# hygiea_v0_0.net
KiCad netlist of a schematic drawn in EAGLE
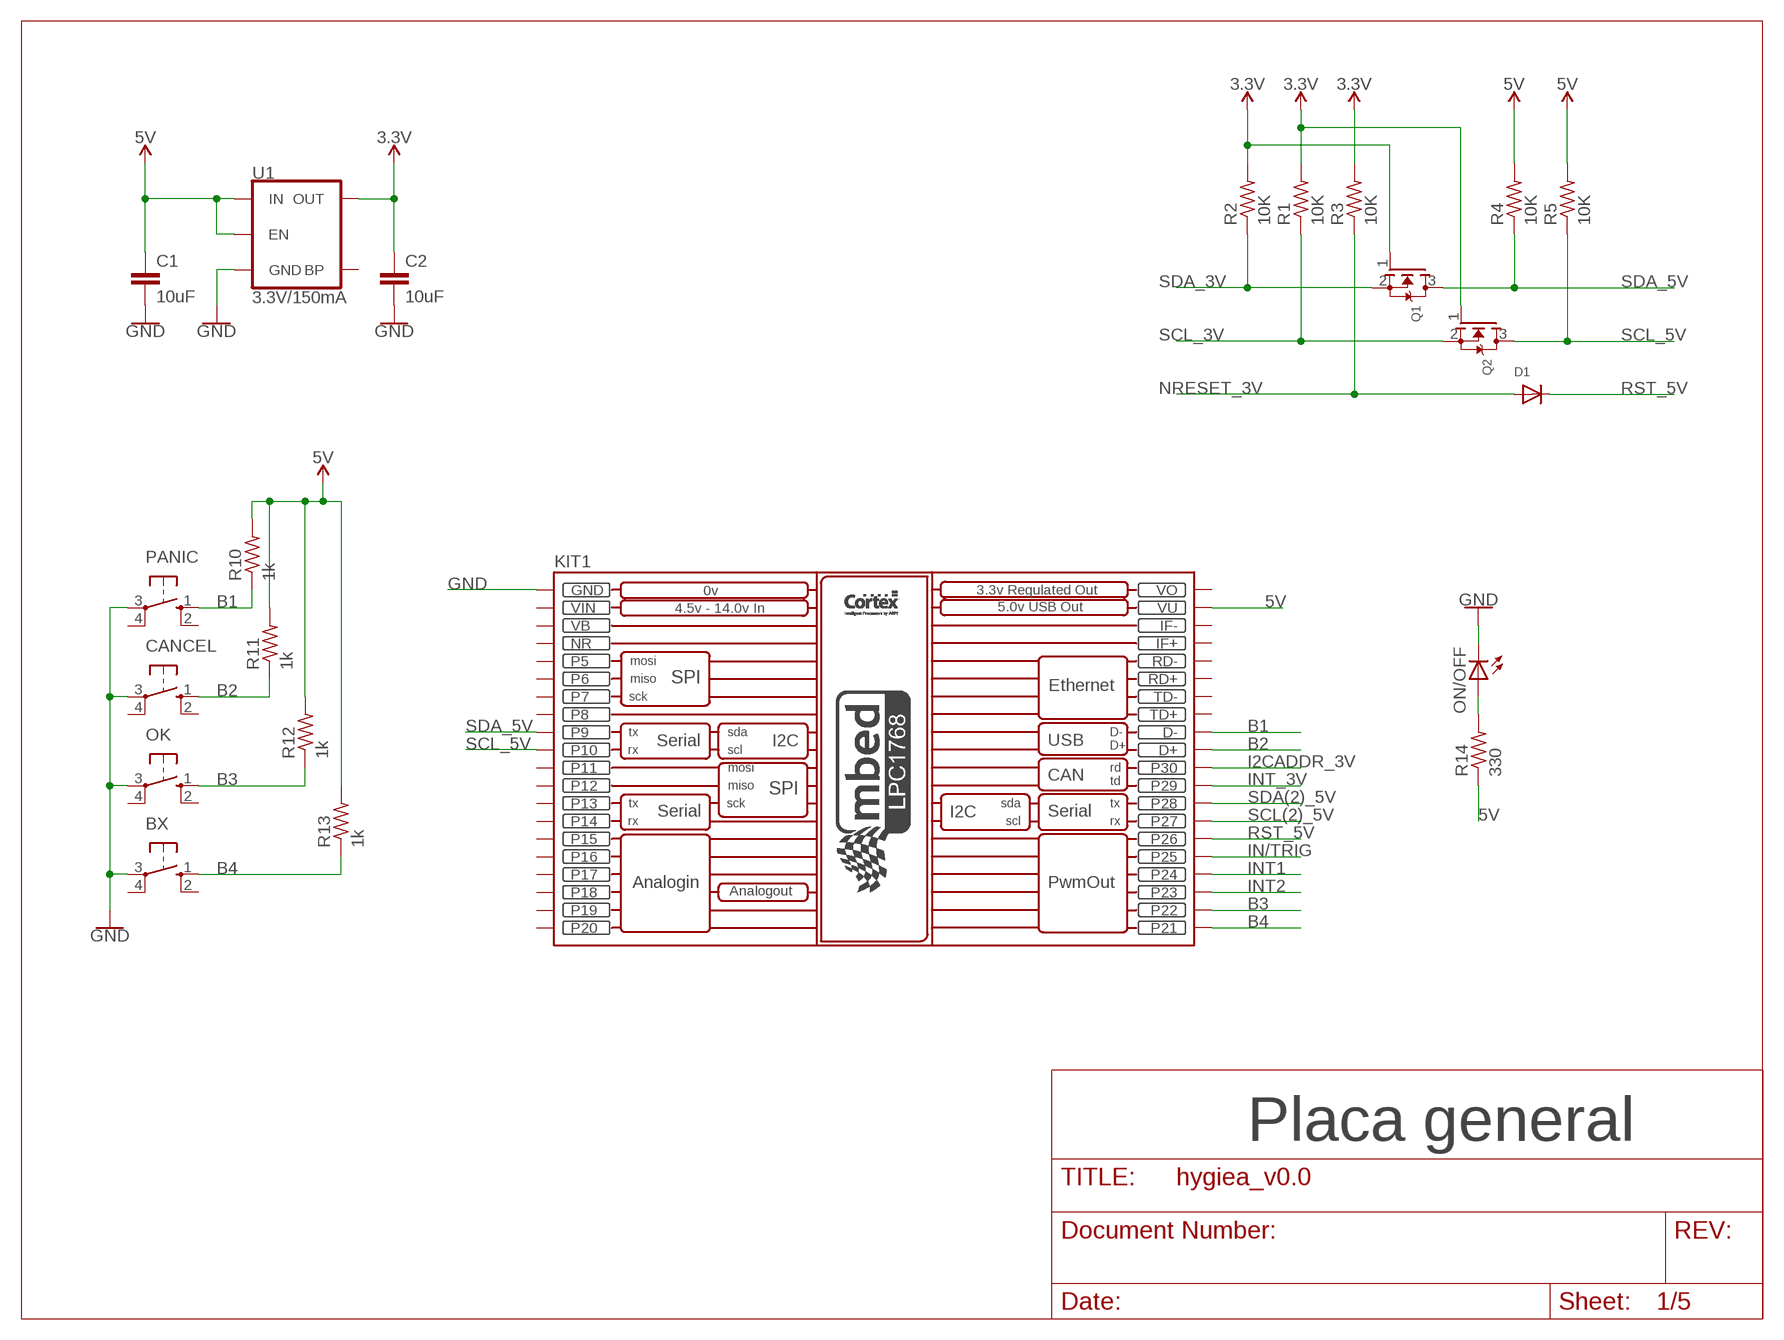
[diagram p0: schematic, sheet 1]
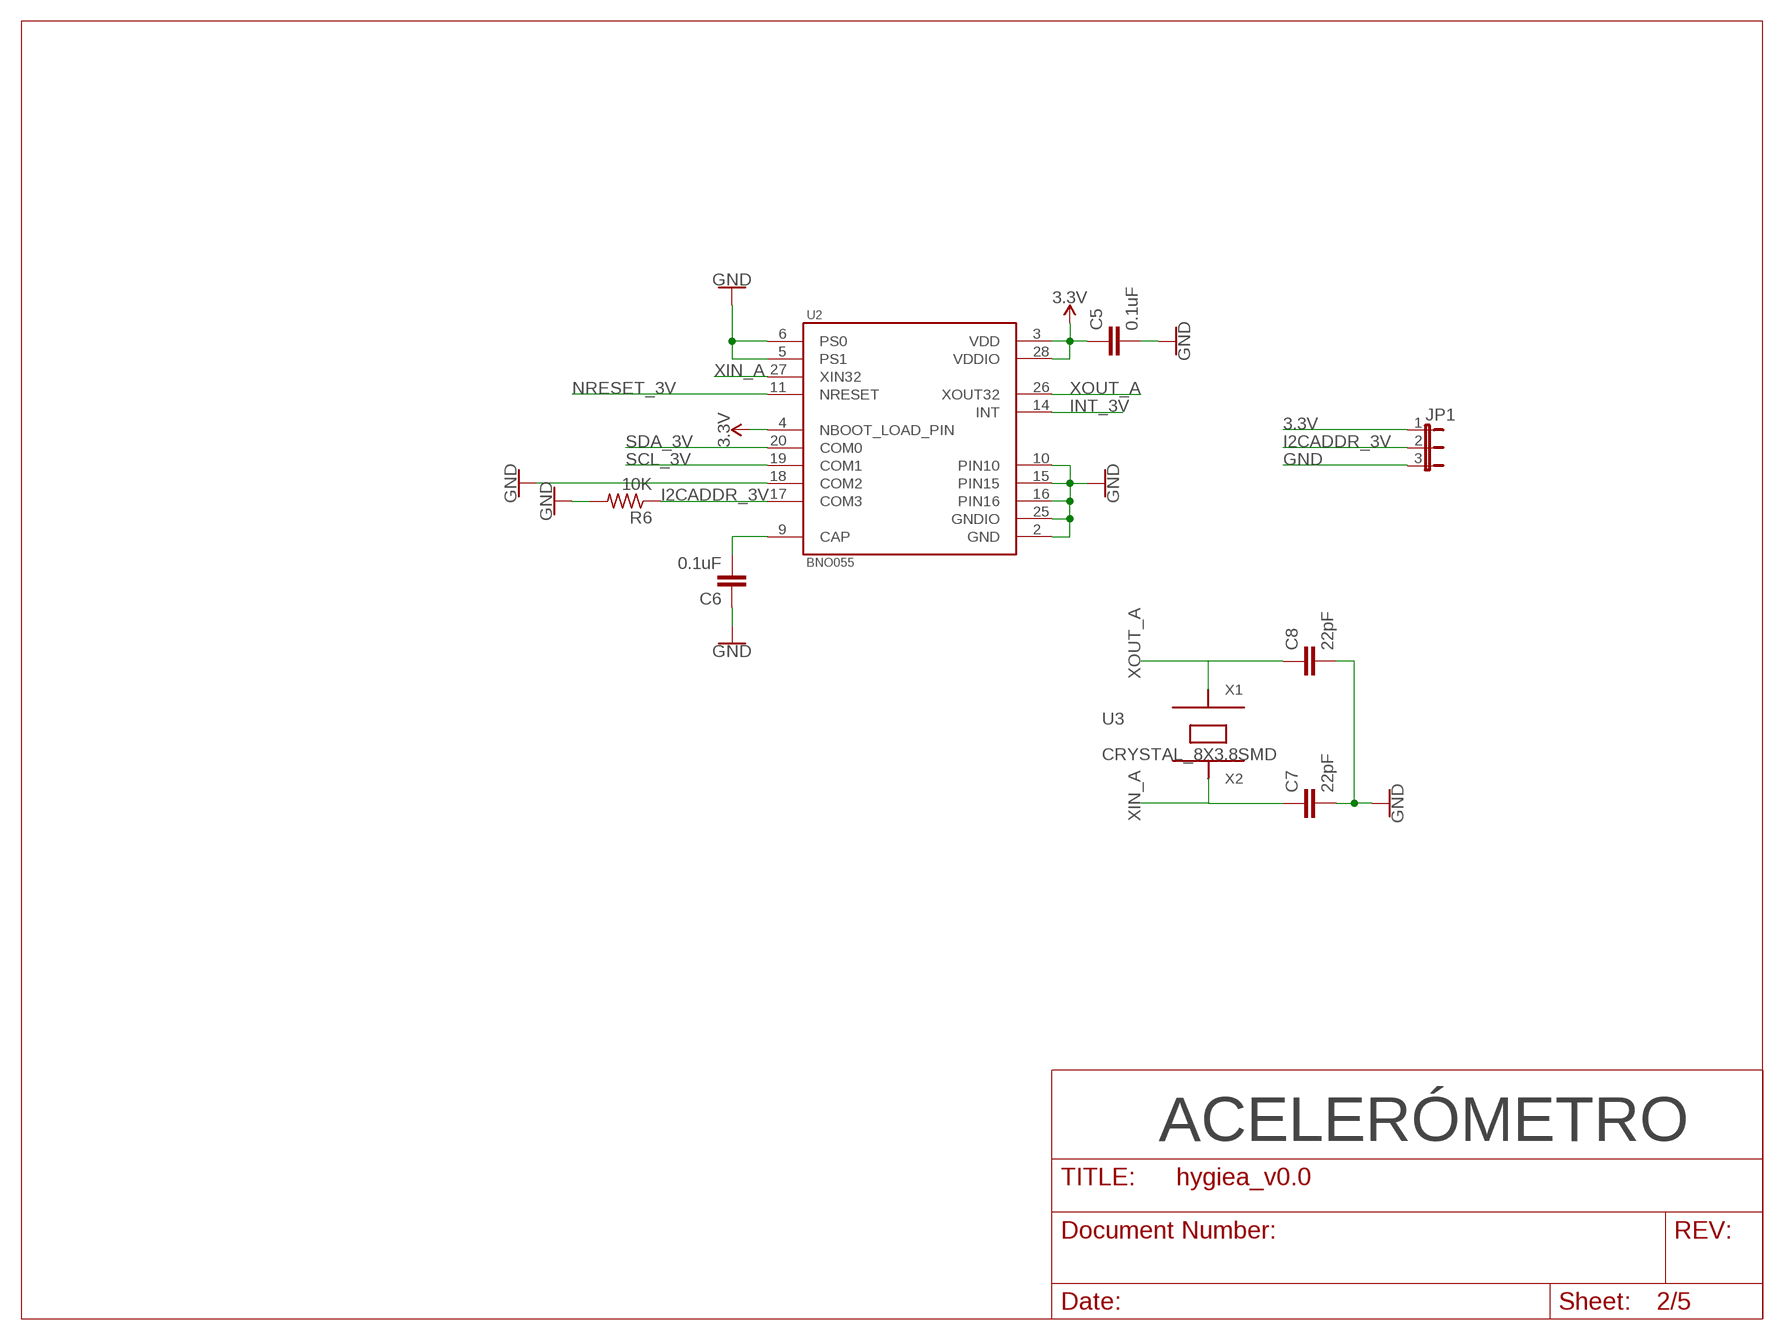
[diagram p1: schematic, sheet 2]
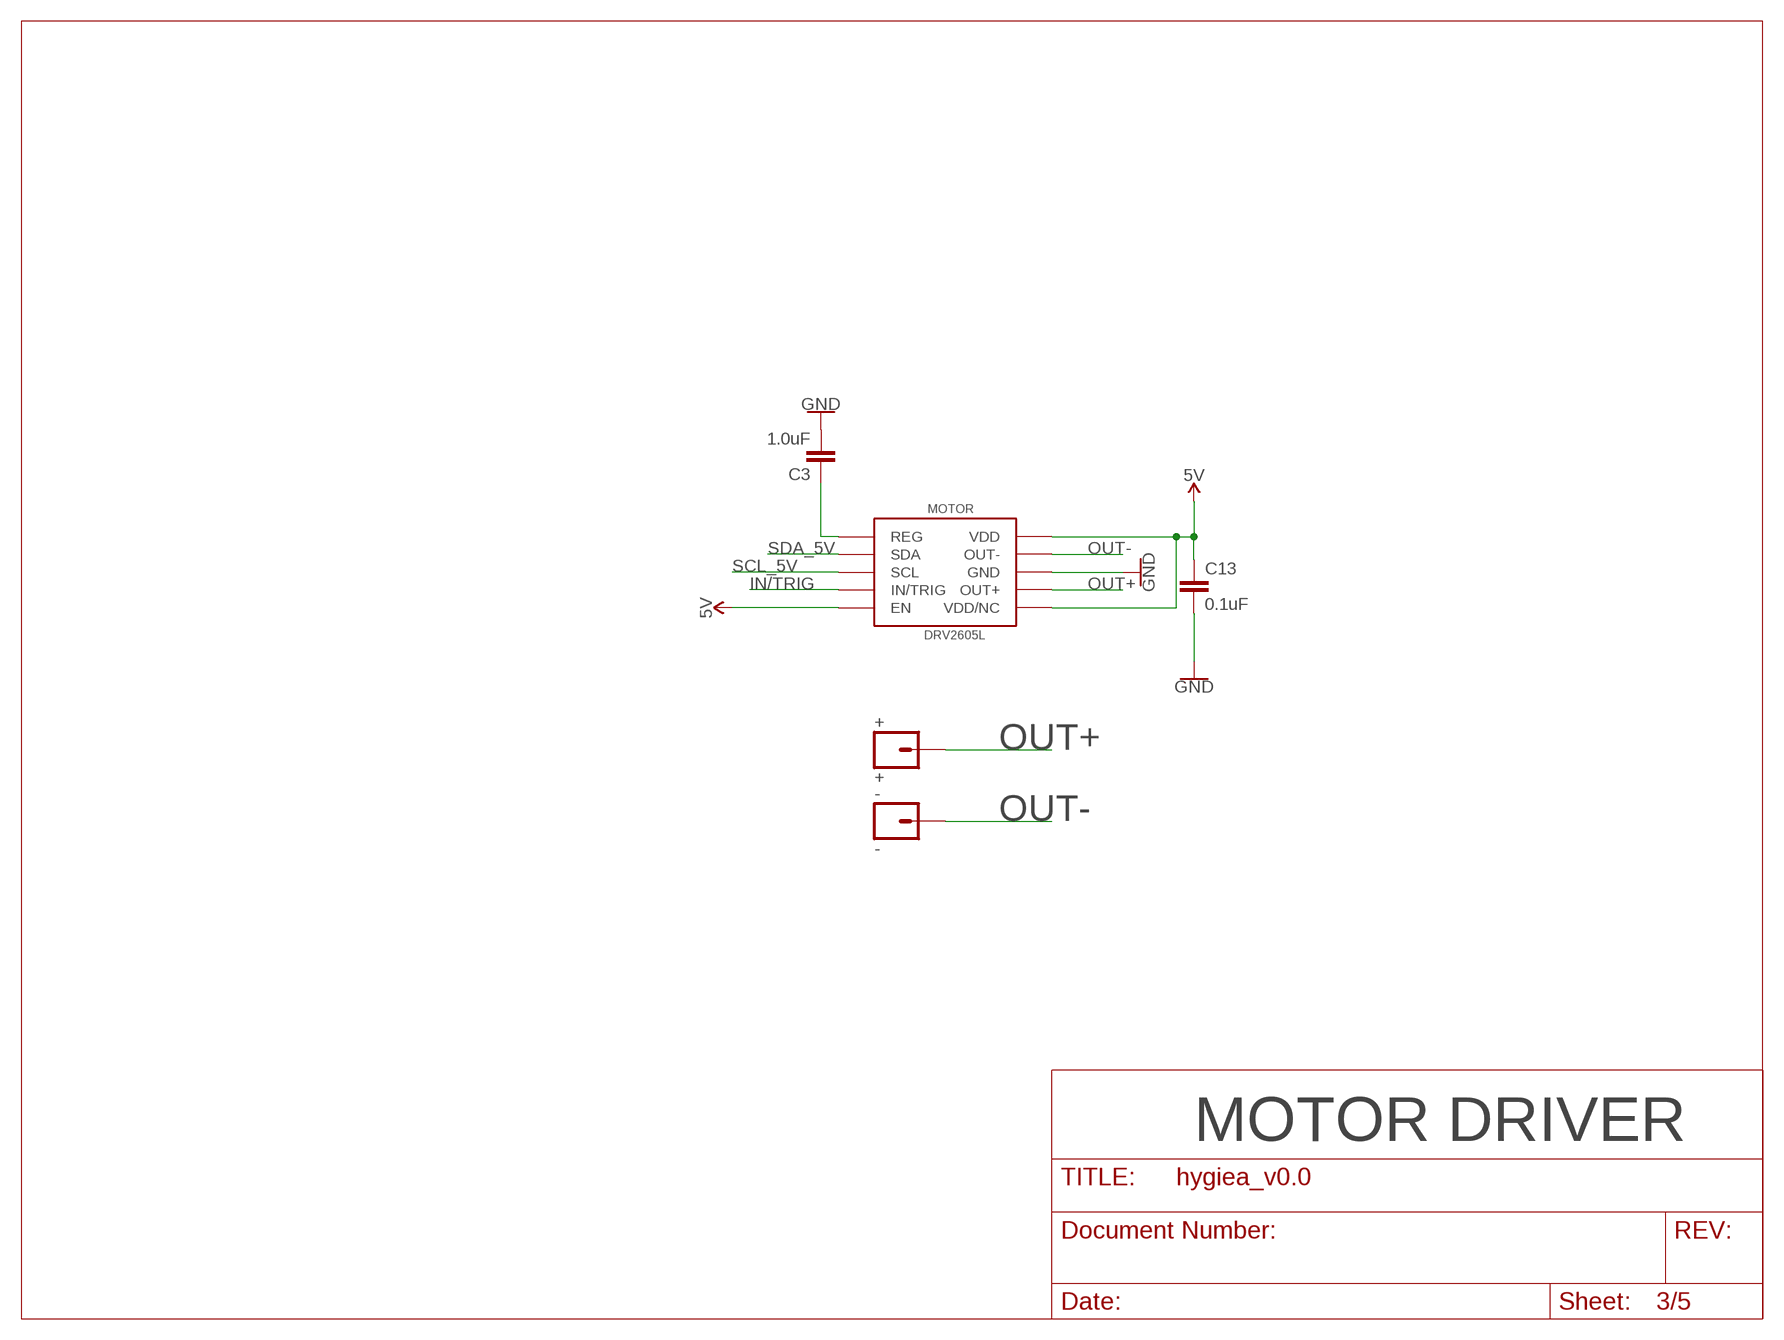
[diagram p2: schematic, sheet 3]
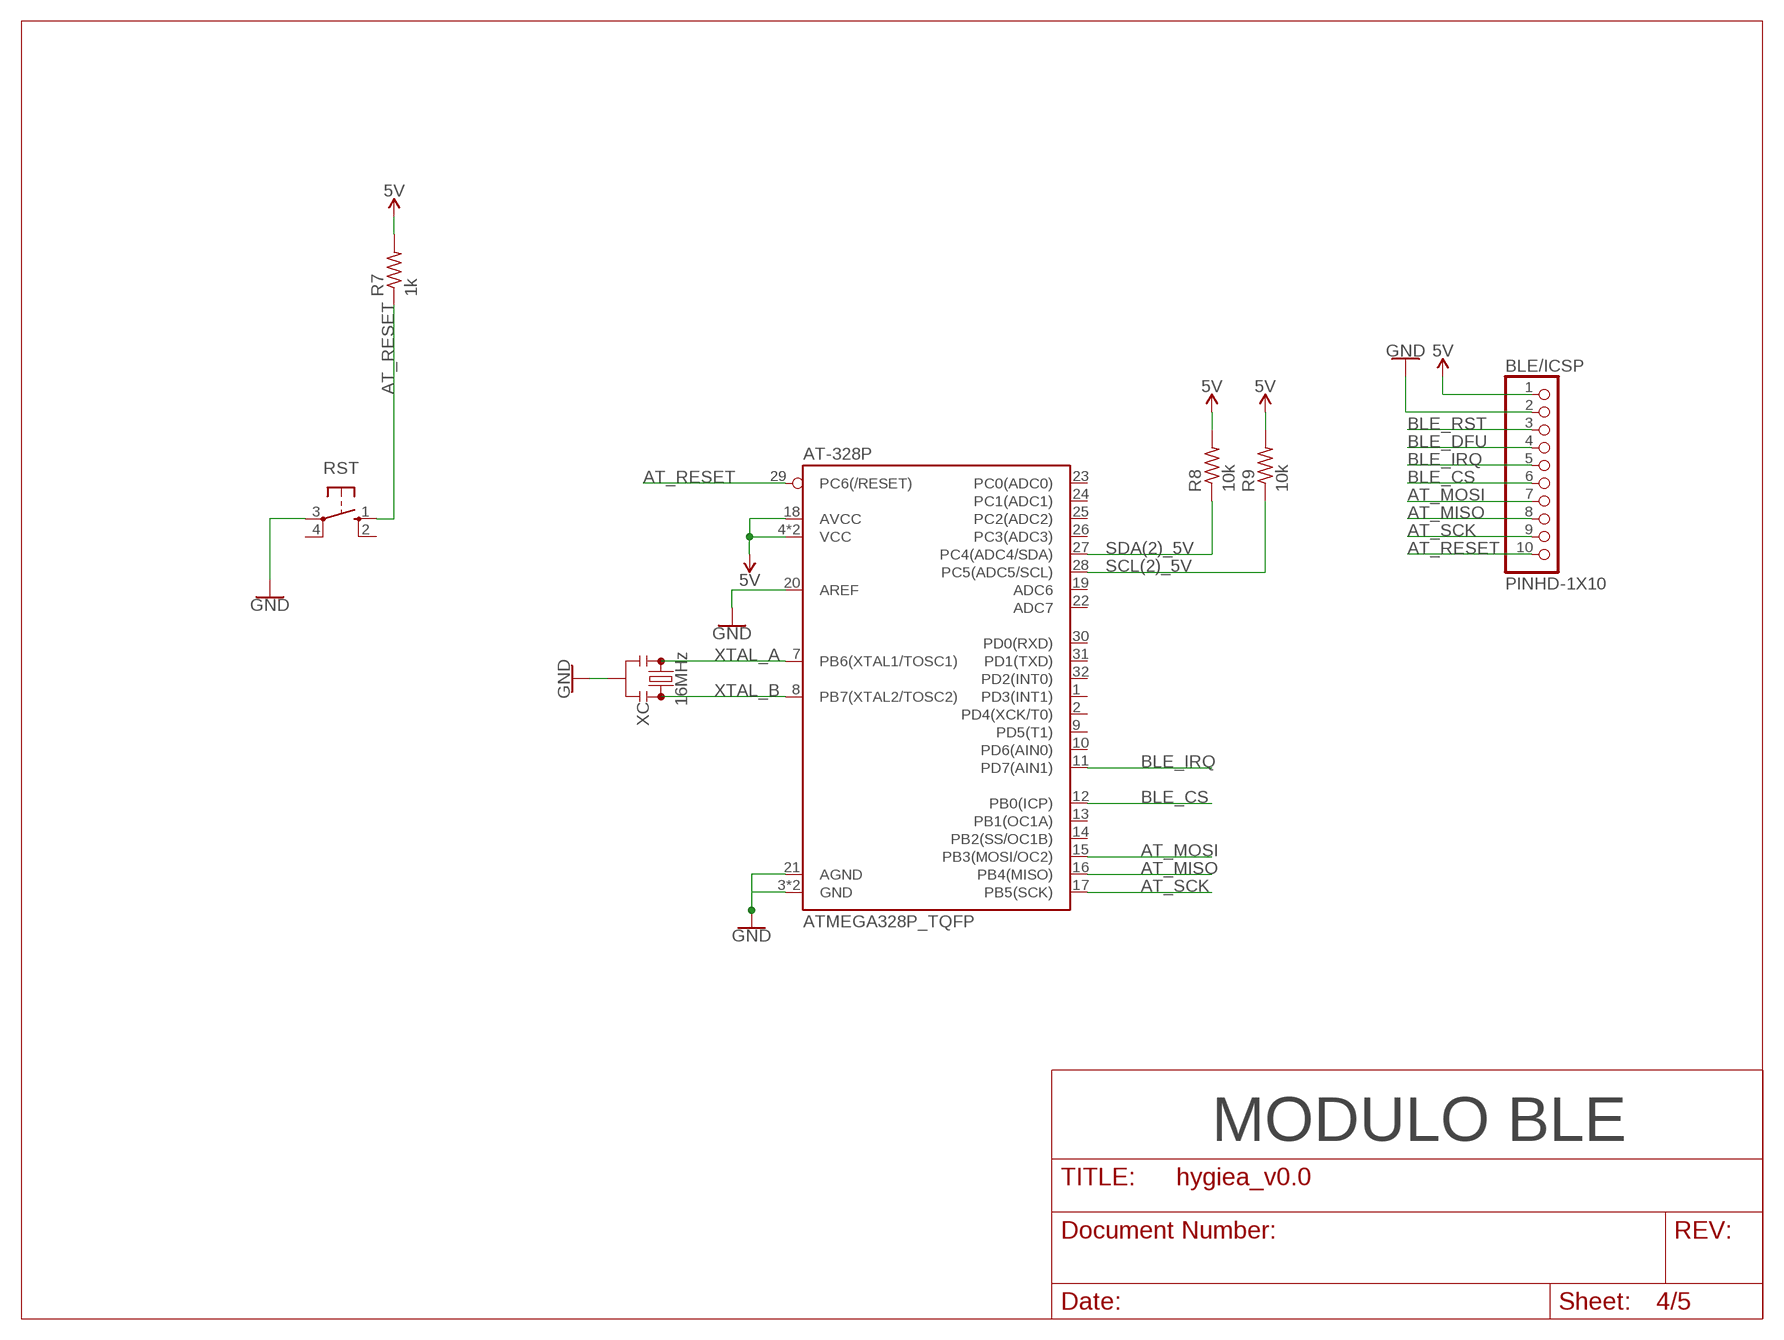
[diagram p3: schematic, sheet 4]
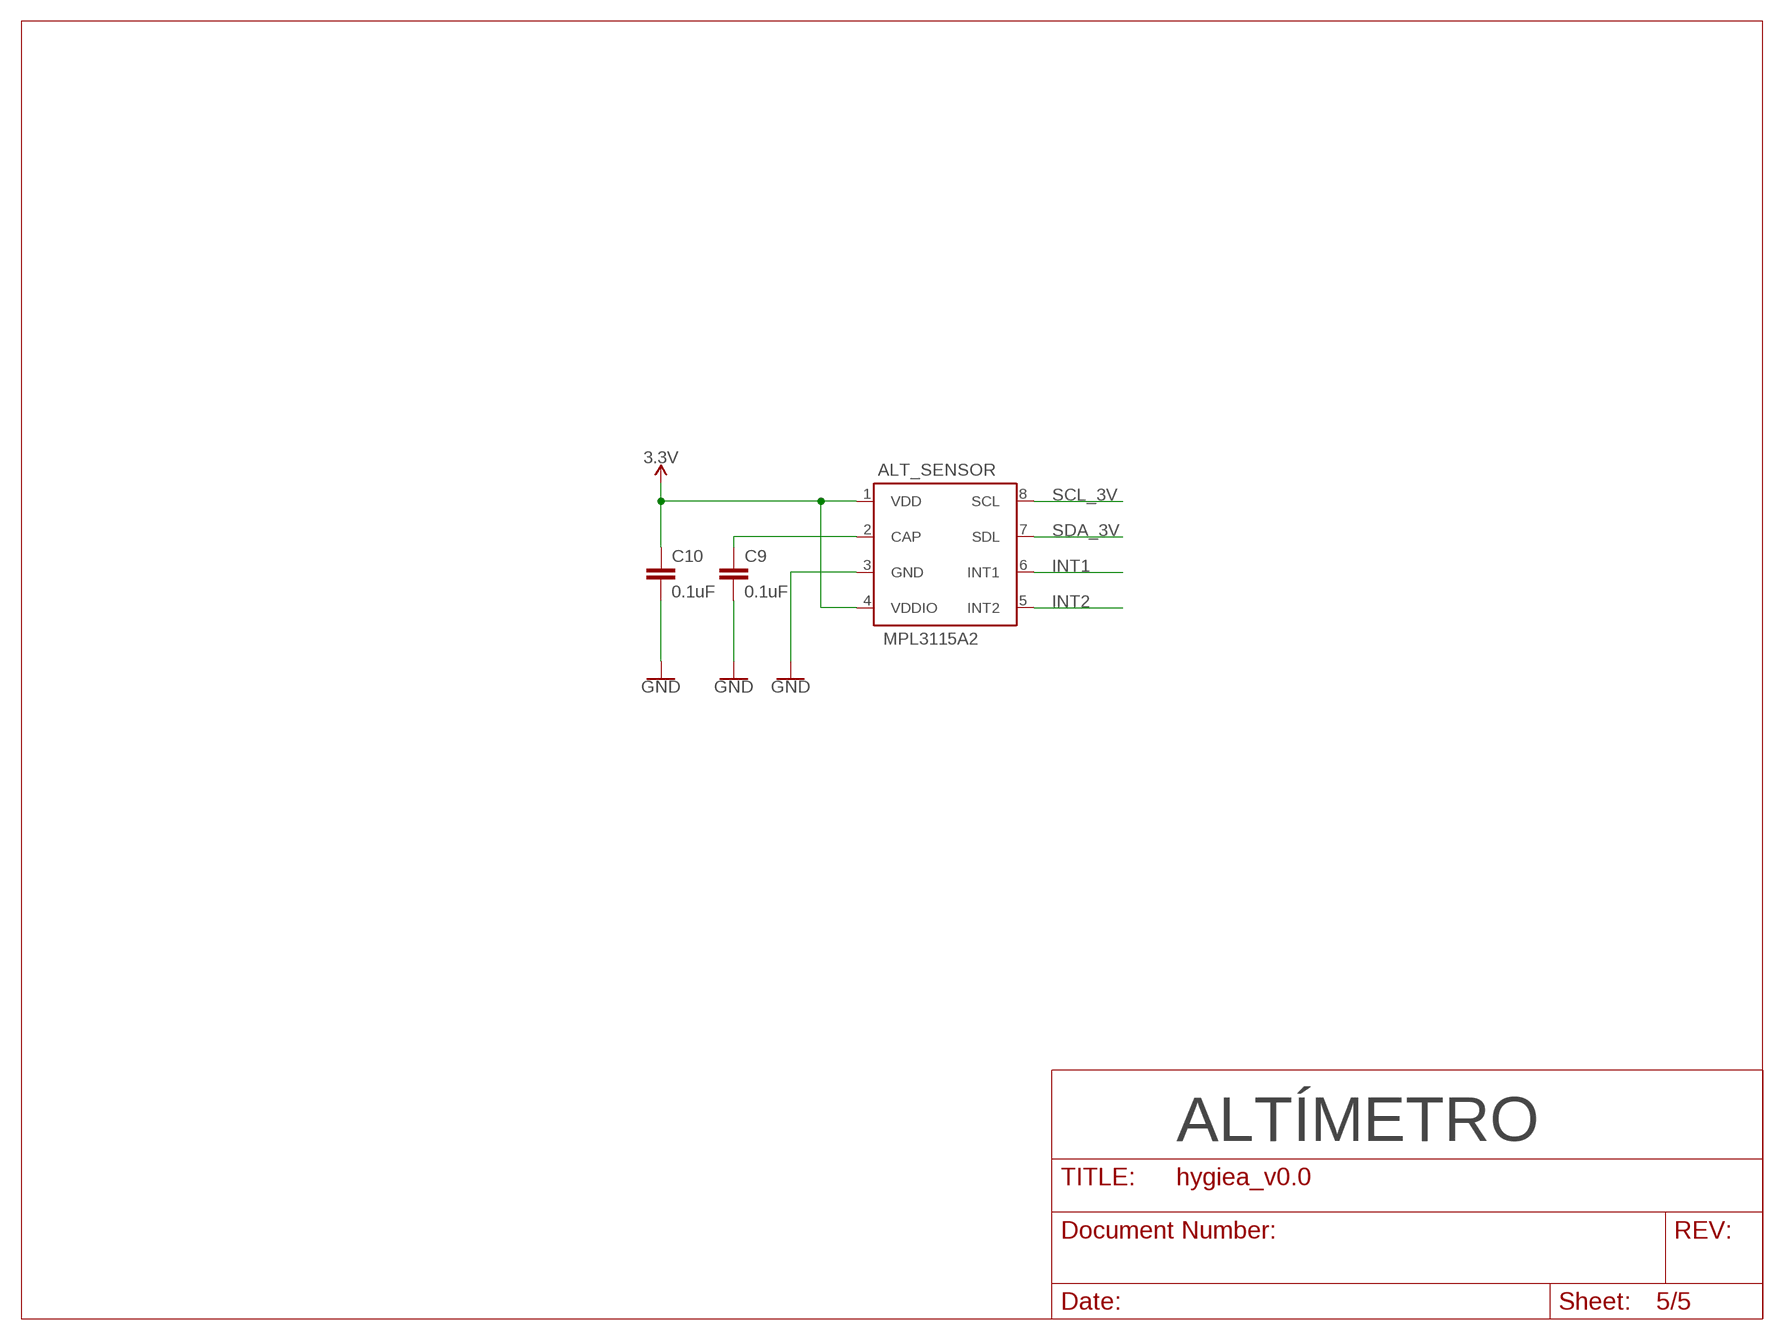
[diagram p4: schematic, sheet 5]

(export (version "E")
  (design (tool "Eeschema 10.0.6"))
  (components
    (comp (ref "BX")
      (value "10-XX")
      (footprint "eagle-import:B3F-10XX")
      (fields (field (name "MPN") "B3F-1000"))
      (libsource (lib "eagle-import") (part "10-XX"))
    )
    (comp (ref "C1")
      (value "10uF")
      (footprint "eagle-import:C0805")
      (libsource (lib "eagle-import") (part "C-EUC0805"))
    )
    (comp (ref "C2")
      (value "10uF")
      (footprint "eagle-import:C0805")
      (libsource (lib "eagle-import") (part "C-EUC0805"))
    )
    (comp (ref "CANCEL")
      (value "10-XX")
      (footprint "eagle-import:B3F-10XX")
      (fields (field (name "MPN") "B3F-1000"))
      (libsource (lib "eagle-import") (part "10-XX"))
    )
    (comp (ref "D1")
      (value "DIODESOD-323F")
      (footprint "eagle-import:SOD-323F")
      (libsource (lib "eagle-import") (part "DIODESOD-323F"))
    )
    (comp (ref "KIT1")
      (value "MBED_NXP_LPC1768")
      (footprint "eagle-import:MBED-KIT")
      (libsource (lib "eagle-import") (part "MBED_NXP_LPC1768"))
    )
    (comp (ref "OK")
      (value "10-XX")
      (footprint "eagle-import:B3F-10XX")
      (fields (field (name "MPN") "B3F-1000"))
      (libsource (lib "eagle-import") (part "10-XX"))
    )
    (comp (ref "ON/OFF")
      (value "LEDCHIP-LED0805")
      (footprint "eagle-import:CHIP-LED0805")
      (libsource (lib "eagle-import") (part "LEDCHIP-LED0805"))
    )
    (comp (ref "PANIC")
      (value "10-XX")
      (footprint "eagle-import:B3F-10XX")
      (fields (field (name "MPN") "B3F-1000"))
      (libsource (lib "eagle-import") (part "10-XX"))
    )
    (comp (ref "Q1")
      (value "MOSFET-NWAVE")
      (footprint "eagle-import:SOT23-W")
      (libsource (lib "eagle-import") (part "MOSFET-NWAVE"))
    )
    (comp (ref "Q2")
      (value "MOSFET-NWAVE")
      (footprint "eagle-import:SOT23-W")
      (libsource (lib "eagle-import") (part "MOSFET-NWAVE"))
    )
    (comp (ref "R1")
      (value "10K")
      (footprint "eagle-import:R0805")
      (libsource (lib "eagle-import") (part "R-US_R0805"))
    )
    (comp (ref "R2")
      (value "10K")
      (footprint "eagle-import:R0805")
      (libsource (lib "eagle-import") (part "R-US_R0805"))
    )
    (comp (ref "R3")
      (value "10K")
      (footprint "eagle-import:R0805")
      (libsource (lib "eagle-import") (part "R-US_R0805"))
    )
    (comp (ref "R4")
      (value "10K")
      (footprint "eagle-import:R0805")
      (libsource (lib "eagle-import") (part "R-US_R0805"))
    )
    (comp (ref "R5")
      (value "10K")
      (footprint "eagle-import:R0805")
      (libsource (lib "eagle-import") (part "R-US_R0805"))
    )
    (comp (ref "R10")
      (value "1k")
      (footprint "eagle-import:R0805")
      (libsource (lib "eagle-import") (part "R-US_R0805"))
    )
    (comp (ref "R11")
      (value "1k")
      (footprint "eagle-import:R0805")
      (libsource (lib "eagle-import") (part "R-US_R0805"))
    )
    (comp (ref "R12")
      (value "1k")
      (footprint "eagle-import:R0805")
      (libsource (lib "eagle-import") (part "R-US_R0805"))
    )
    (comp (ref "R13")
      (value "1k")
      (footprint "eagle-import:R0805")
      (libsource (lib "eagle-import") (part "R-US_R0805"))
    )
    (comp (ref "R14")
      (value "330")
      (footprint "eagle-import:R0805")
      (libsource (lib "eagle-import") (part "R-US_R0805"))
    )
    (comp (ref "U1")
      (value "3.3V/150mA")
      (footprint "eagle-import:SOT23-5")
      (libsource (lib "eagle-import") (part "V_REG_MIC52053.3V"))
    )
    (comp (ref "C5")
      (value "0.1uF")
      (footprint "eagle-import:C0805")
      (libsource (lib "eagle-import") (part "C-EUC0805"))
    )
    (comp (ref "C6")
      (value "0.1uF")
      (footprint "eagle-import:C0805")
      (libsource (lib "eagle-import") (part "C-EUC0805"))
    )
    (comp (ref "C7")
      (value "22pF")
      (footprint "eagle-import:C0805")
      (libsource (lib "eagle-import") (part "C-EUC0805"))
    )
    (comp (ref "C8")
      (value "22pF")
      (footprint "eagle-import:C0805")
      (libsource (lib "eagle-import") (part "C-EUC0805"))
    )
    (comp (ref "JP1")
      (value "JP2E")
      (footprint "eagle-import:JP2")
      (libsource (lib "eagle-import") (part "JP2E"))
    )
    (comp (ref "R6")
      (value "10K")
      (footprint "eagle-import:R0805")
      (libsource (lib "eagle-import") (part "R-US_R0805"))
    )
    (comp (ref "U2")
      (value "BNO055")
      (footprint "eagle-import:LGA28R50P4X10_380X520X100")
      (fields (field (name "DIGI-KEY_PART_NUMBER") "828-1058-1-ND") (field (name "MF") "Bosch"))
      (libsource (lib "eagle-import") (part "BNO055"))
    )
    (comp (ref "U3")
      (value "CRYSTAL_8X3.8SMD")
      (footprint "eagle-import:PM8.0X3.8MM")
      (libsource (lib "eagle-import") (part "CRYSTAL_8X3.8SMD"))
    )
    (comp (ref "AT-328P")
      (value "ATMEGA328P_TQFP")
      (footprint "eagle-import:TQFP32-08")
      (libsource (lib "eagle-import") (part "ATMEGA328P_TQFP"))
    )
    (comp (ref "BLE/ICSP")
      (value "PINHD-1X10")
      (footprint "eagle-import:1X10-BIG")
      (libsource (lib "eagle-import") (part "PINHD-1X10"))
    )
    (comp (ref "R7")
      (value "1k")
      (footprint "eagle-import:R0805")
      (libsource (lib "eagle-import") (part "R-US_R0805"))
    )
    (comp (ref "R8")
      (value "10k")
      (footprint "eagle-import:R0805")
      (libsource (lib "eagle-import") (part "R-US_R0805"))
    )
    (comp (ref "R9")
      (value "10k")
      (footprint "eagle-import:R0805")
      (libsource (lib "eagle-import") (part "R-US_R0805"))
    )
    (comp (ref "RST")
      (value "10-XX")
      (footprint "eagle-import:B3F-10XX")
      (fields (field (name "MPN") "B3F-1000"))
      (libsource (lib "eagle-import") (part "10-XX"))
    )
    (comp (ref "XC")
      (value "16MHz")
      (footprint "eagle-import:RESONATOR-SMD-3.2X1.3")
      (libsource (lib "eagle-import") (part "RESONATOR-16MHZSMD_3.2X1.3"))
    )
    (comp (ref "ALT_SENSOR")
      (value "MPL3115A2")
      (footprint "eagle-import:LGA8")
      (libsource (lib "eagle-import") (part "MPL3115A2"))
    )
    (comp (ref "C9")
      (value "0.1uF")
      (footprint "eagle-import:C0805")
      (libsource (lib "eagle-import") (part "C-EUC0805"))
    )
    (comp (ref "C10")
      (value "0.1uF")
      (footprint "eagle-import:C0805")
      (libsource (lib "eagle-import") (part "C-EUC0805"))
    )
    (comp (ref "+")
      (value "+")
      (footprint "eagle-import:1X01_OFFSET")
      (libsource (lib "eagle-import") (part "CONN_01OFFSET"))
    )
    (comp (ref "-")
      (value "-")
      (footprint "eagle-import:1X01_OFFSET")
      (libsource (lib "eagle-import") (part "CONN_01OFFSET"))
    )
    (comp (ref "C3")
      (value "1.0uF")
      (footprint "eagle-import:C0805")
      (libsource (lib "eagle-import") (part "C-EUC0805"))
    )
    (comp (ref "C13")
      (value "0.1uF")
      (footprint "eagle-import:C0805")
      (libsource (lib "eagle-import") (part "C-EUC0805"))
    )
    (comp (ref "MOTOR")
      (value "DRV2605L")
      (footprint "eagle-import:VSSOP-10")
      (libsource (lib "eagle-import") (part "DRV2605L"))
    )
  )
  (nets
    (net (code "1") (name "3.3V") (class "Default")
      (node (ref "ALT_SENSOR") (pin "1") (pinfunction "VDD_1") (pintype "power_in"))
      (node (ref "ALT_SENSOR") (pin "4") (pinfunction "VDDIO_4") (pintype "power_in"))
      (node (ref "C10") (pin "1") (pinfunction "1_1") (pintype "passive"))
      (node (ref "C2") (pin "1") (pinfunction "1_1") (pintype "passive"))
      (node (ref "C5") (pin "1") (pinfunction "1_1") (pintype "passive"))
      (node (ref "JP1") (pin "1") (pinfunction "1_1") (pintype "passive"))
      (node (ref "Q1") (pin "1") (pinfunction "G_1") (pintype "bidirectional"))
      (node (ref "Q2") (pin "1") (pinfunction "G_1") (pintype "bidirectional"))
      (node (ref "R1") (pin "2") (pinfunction "2_2") (pintype "passive"))
      (node (ref "R2") (pin "2") (pinfunction "2_2") (pintype "passive"))
      (node (ref "R3") (pin "2") (pinfunction "2_2") (pintype "passive"))
      (node (ref "U1") (pin "5") (pinfunction "OUT_5") (pintype "passive"))
      (node (ref "U2") (pin "28") (pinfunction "VDDIO_28") (pintype "power_in"))
      (node (ref "U2") (pin "3") (pinfunction "VDD_3") (pintype "power_in"))
      (node (ref "U2") (pin "4") (pinfunction "NBOOT_LOAD_PIN_4") (pintype "bidirectional"))
    )
    (net (code "2") (name "5V") (class "Default")
      (node (ref "AT-328P") (pin "18") (pinfunction "AVCC_18") (pintype "bidirectional"))
      (node (ref "AT-328P") (pin "4") (pinfunction "VCC_4") (pintype "bidirectional"))
      (node (ref "AT-328P") (pin "6") (pinfunction "VCC_6") (pintype "bidirectional"))
      (node (ref "BLE/ICSP") (pin "1") (pinfunction "1_1") (pintype "passive"))
      (node (ref "C1") (pin "1") (pinfunction "1_1") (pintype "passive"))
      (node (ref "C13") (pin "1") (pinfunction "1_1") (pintype "passive"))
      (node (ref "KIT1") (pin "VU") (pinfunction "VU_VU") (pintype "power_in"))
      (node (ref "MOTOR") (pin "P$10") (pinfunction "VDD_P$10") (pintype "bidirectional"))
      (node (ref "MOTOR") (pin "P$5") (pinfunction "EN_P$5") (pintype "bidirectional"))
      (node (ref "MOTOR") (pin "P$6") (pinfunction "VDD/NC_P$6") (pintype "bidirectional"))
      (node (ref "R10") (pin "2") (pinfunction "2_2") (pintype "passive"))
      (node (ref "R11") (pin "2") (pinfunction "2_2") (pintype "passive"))
      (node (ref "R12") (pin "2") (pinfunction "2_2") (pintype "passive"))
      (node (ref "R13") (pin "2") (pinfunction "2_2") (pintype "passive"))
      (node (ref "R14") (pin "1") (pinfunction "1_1") (pintype "passive"))
      (node (ref "R4") (pin "2") (pinfunction "2_2") (pintype "passive"))
      (node (ref "R5") (pin "2") (pinfunction "2_2") (pintype "passive"))
      (node (ref "R7") (pin "2") (pinfunction "2_2") (pintype "passive"))
      (node (ref "R8") (pin "2") (pinfunction "2_2") (pintype "passive"))
      (node (ref "R9") (pin "2") (pinfunction "2_2") (pintype "passive"))
      (node (ref "U1") (pin "1") (pinfunction "IN_1") (pintype "input"))
      (node (ref "U1") (pin "3") (pinfunction "EN_3") (pintype "input"))
    )
    (net (code "3") (name "AT_MISO") (class "Default")
      (node (ref "AT-328P") (pin "16") (pinfunction "PB4(MISO)_16") (pintype "bidirectional"))
      (node (ref "BLE/ICSP") (pin "8") (pinfunction "8_8") (pintype "passive"))
    )
    (net (code "4") (name "AT_MOSI") (class "Default")
      (node (ref "AT-328P") (pin "15") (pinfunction "PB3(MOSI/OC2)_15") (pintype "bidirectional"))
      (node (ref "BLE/ICSP") (pin "7") (pinfunction "7_7") (pintype "passive"))
    )
    (net (code "5") (name "AT_RESET") (class "Default")
      (node (ref "AT-328P") (pin "29") (pinfunction "PC6(/RESET)_29") (pintype "bidirectional"))
      (node (ref "BLE/ICSP") (pin "10") (pinfunction "10_10") (pintype "passive"))
      (node (ref "R7") (pin "1") (pinfunction "1_1") (pintype "passive"))
      (node (ref "RST") (pin "1") (pinfunction "S_1") (pintype "passive"))
    )
    (net (code "6") (name "AT_SCK") (class "Default")
      (node (ref "AT-328P") (pin "17") (pinfunction "PB5(SCK)_17") (pintype "bidirectional"))
      (node (ref "BLE/ICSP") (pin "9") (pinfunction "9_9") (pintype "passive"))
    )
    (net (code "7") (name "B1") (class "Default")
      (node (ref "KIT1") (pin "D-") (pinfunction "D-_D-") (pintype "bidirectional"))
      (node (ref "PANIC") (pin "1") (pinfunction "S_1") (pintype "passive"))
      (node (ref "R10") (pin "1") (pinfunction "1_1") (pintype "passive"))
    )
    (net (code "8") (name "B2") (class "Default")
      (node (ref "CANCEL") (pin "1") (pinfunction "S_1") (pintype "passive"))
      (node (ref "KIT1") (pin "D+") (pinfunction "D+_D+") (pintype "bidirectional"))
      (node (ref "R11") (pin "1") (pinfunction "1_1") (pintype "passive"))
    )
    (net (code "9") (name "B3") (class "Default")
      (node (ref "KIT1") (pin "P$22") (pinfunction "P22_P$22") (pintype "bidirectional"))
      (node (ref "OK") (pin "1") (pinfunction "S_1") (pintype "passive"))
      (node (ref "R12") (pin "1") (pinfunction "1_1") (pintype "passive"))
    )
    (net (code "10") (name "B4") (class "Default")
      (node (ref "BX") (pin "1") (pinfunction "S_1") (pintype "passive"))
      (node (ref "KIT1") (pin "P$21") (pinfunction "P21_P$21") (pintype "bidirectional"))
      (node (ref "R13") (pin "1") (pinfunction "1_1") (pintype "passive"))
    )
    (net (code "11") (name "BLE_CS") (class "Default")
      (node (ref "AT-328P") (pin "12") (pinfunction "PB0(ICP)_12") (pintype "bidirectional"))
      (node (ref "BLE/ICSP") (pin "6") (pinfunction "6_6") (pintype "passive"))
    )
    (net (code "12") (name "BLE_DFU") (class "Default")
      (node (ref "BLE/ICSP") (pin "4") (pinfunction "4_4") (pintype "passive"))
    )
    (net (code "13") (name "BLE_IRQ") (class "Default")
      (node (ref "AT-328P") (pin "11") (pinfunction "PD7(AIN1)_11") (pintype "bidirectional"))
      (node (ref "BLE/ICSP") (pin "5") (pinfunction "5_5") (pintype "passive"))
    )
    (net (code "14") (name "BLE_RST") (class "Default")
      (node (ref "BLE/ICSP") (pin "3") (pinfunction "3_3") (pintype "passive"))
    )
    (net (code "15") (name "GND") (class "Default")
      (node (ref "ALT_SENSOR") (pin "3") (pinfunction "GND_3") (pintype "power_in"))
      (node (ref "AT-328P") (pin "20") (pinfunction "AREF_20") (pintype "bidirectional"))
      (node (ref "AT-328P") (pin "21") (pinfunction "AGND_21") (pintype "bidirectional"))
      (node (ref "AT-328P") (pin "3") (pinfunction "GND_3") (pintype "bidirectional"))
      (node (ref "AT-328P") (pin "5") (pinfunction "GND_5") (pintype "bidirectional"))
      (node (ref "BLE/ICSP") (pin "2") (pinfunction "2_2") (pintype "passive"))
      (node (ref "BX") (pin "3") (pinfunction "P_3") (pintype "passive"))
      (node (ref "C1") (pin "2") (pinfunction "2_2") (pintype "passive"))
      (node (ref "C10") (pin "2") (pinfunction "2_2") (pintype "passive"))
      (node (ref "C13") (pin "2") (pinfunction "2_2") (pintype "passive"))
      (node (ref "C2") (pin "2") (pinfunction "2_2") (pintype "passive"))
      (node (ref "C3") (pin "2") (pinfunction "2_2") (pintype "passive"))
      (node (ref "C5") (pin "2") (pinfunction "2_2") (pintype "passive"))
      (node (ref "C6") (pin "1") (pinfunction "1_1") (pintype "passive"))
      (node (ref "C7") (pin "2") (pinfunction "2_2") (pintype "passive"))
      (node (ref "C8") (pin "2") (pinfunction "2_2") (pintype "passive"))
      (node (ref "C9") (pin "2") (pinfunction "2_2") (pintype "passive"))
      (node (ref "CANCEL") (pin "3") (pinfunction "P_3") (pintype "passive"))
      (node (ref "JP1") (pin "3") (pinfunction "3_3") (pintype "passive"))
      (node (ref "KIT1") (pin "GND") (pinfunction "GND_GND") (pintype "power_in"))
      (node (ref "MOTOR") (pin "P$8") (pinfunction "GND_P$8") (pintype "bidirectional"))
      (node (ref "OK") (pin "3") (pinfunction "P_3") (pintype "passive"))
      (node (ref "ON/OFF") (pin "C") (pinfunction "C_C") (pintype "passive"))
      (node (ref "PANIC") (pin "3") (pinfunction "P_3") (pintype "passive"))
      (node (ref "R6") (pin "2") (pinfunction "2_2") (pintype "passive"))
      (node (ref "RST") (pin "3") (pinfunction "P_3") (pintype "passive"))
      (node (ref "U1") (pin "2") (pinfunction "GND_2") (pintype "input"))
      (node (ref "U2") (pin "10") (pinfunction "PIN10_10") (pintype "power_in"))
      (node (ref "U2") (pin "15") (pinfunction "PIN15_15") (pintype "power_in"))
      (node (ref "U2") (pin "16") (pinfunction "PIN16_16") (pintype "power_in"))
      (node (ref "U2") (pin "18") (pinfunction "COM2_18") (pintype "bidirectional"))
      (node (ref "U2") (pin "2") (pinfunction "GND_2") (pintype "power_in"))
      (node (ref "U2") (pin "25") (pinfunction "GNDIO_25") (pintype "power_in"))
      (node (ref "U2") (pin "5") (pinfunction "PS1_5") (pintype "input"))
      (node (ref "U2") (pin "6") (pinfunction "PS0_6") (pintype "input"))
      (node (ref "XC") (pin "2") (pinfunction "2_2") (pintype "passive"))
    )
    (net (code "16") (name "I2CADDR_3V") (class "Default")
      (node (ref "JP1") (pin "2") (pinfunction "2_2") (pintype "passive"))
      (node (ref "KIT1") (pin "P$30") (pinfunction "P30_P$30") (pintype "bidirectional"))
      (node (ref "R6") (pin "1") (pinfunction "1_1") (pintype "passive"))
      (node (ref "U2") (pin "17") (pinfunction "COM3_17") (pintype "bidirectional"))
    )
    (net (code "17") (name "INT1") (class "Default")
      (node (ref "ALT_SENSOR") (pin "6") (pinfunction "INT1_6") (pintype "bidirectional"))
      (node (ref "KIT1") (pin "P$24") (pinfunction "P24_P$24") (pintype "bidirectional"))
    )
    (net (code "18") (name "INT2") (class "Default")
      (node (ref "ALT_SENSOR") (pin "5") (pinfunction "INT2_5") (pintype "bidirectional"))
      (node (ref "KIT1") (pin "P$23") (pinfunction "P23_P$23") (pintype "bidirectional"))
    )
    (net (code "19") (name "INT_3V") (class "Default")
      (node (ref "KIT1") (pin "P$29") (pinfunction "P29_P$29") (pintype "bidirectional"))
      (node (ref "U2") (pin "14") (pinfunction "INT_14") (pintype "output"))
    )
    (net (code "20") (name "IN{slash}TRIG") (class "Default")
      (node (ref "KIT1") (pin "P$25") (pinfunction "P25_P$25") (pintype "bidirectional"))
      (node (ref "MOTOR") (pin "P$4") (pinfunction "IN/TRIG_P$4") (pintype "bidirectional"))
    )
    (net (code "21") (name "NR") (class "Default")
      (node (ref "KIT1") (pin "NR") (pinfunction "NR_NR") (pintype "power_in"))
    )
    (net (code "22") (name "NRESET_3V") (class "Default")
      (node (ref "D1") (pin "A") (pinfunction "A_A") (pintype "passive"))
      (node (ref "R3") (pin "1") (pinfunction "1_1") (pintype "passive"))
      (node (ref "U2") (pin "11") (pinfunction "NRESET_11") (pintype "input"))
    )
    (net (code "23") (name "Net-(ALT_SENSOR-CAP)") (class "Default")
      (node (ref "ALT_SENSOR") (pin "2") (pinfunction "CAP_2") (pintype "bidirectional"))
      (node (ref "C9") (pin "1") (pinfunction "1_1") (pintype "passive"))
    )
    (net (code "24") (name "Net-(MOTOR-REG)") (class "Default")
      (node (ref "C3") (pin "1") (pinfunction "1_1") (pintype "passive"))
      (node (ref "MOTOR") (pin "P$1") (pinfunction "REG_P$1") (pintype "bidirectional"))
    )
    (net (code "25") (name "Net-(ON/OFF-PadA)") (class "Default")
      (node (ref "ON/OFF") (pin "A") (pinfunction "A_A") (pintype "passive"))
      (node (ref "R14") (pin "2") (pinfunction "2_2") (pintype "passive"))
    )
    (net (code "26") (name "Net-(U2-CAP)") (class "Default")
      (node (ref "C6") (pin "2") (pinfunction "2_2") (pintype "passive"))
      (node (ref "U2") (pin "9") (pinfunction "CAP_9") (pintype "passive"))
    )
    (net (code "27") (name "OUT+") (class "Default")
      (node (ref "+") (pin "1") (pinfunction "1_1") (pintype "passive"))
      (node (ref "MOTOR") (pin "P$7") (pinfunction "OUT+_P$7") (pintype "bidirectional"))
    )
    (net (code "28") (name "OUT-") (class "Default")
      (node (ref "-") (pin "1") (pinfunction "1_1") (pintype "passive"))
      (node (ref "MOTOR") (pin "P$9") (pinfunction "OUT-_P$9") (pintype "bidirectional"))
    )
    (net (code "29") (name "RST_5V") (class "Default")
      (node (ref "D1") (pin "C") (pinfunction "C_C") (pintype "passive"))
      (node (ref "KIT1") (pin "P$26") (pinfunction "P26_P$26") (pintype "bidirectional"))
    )
    (net (code "30") (name "SCL(2)_5V") (class "Default")
      (node (ref "AT-328P") (pin "28") (pinfunction "PC5(ADC5/SCL)_28") (pintype "bidirectional"))
      (node (ref "KIT1") (pin "P$27") (pinfunction "P27_P$27") (pintype "bidirectional"))
      (node (ref "R9") (pin "1") (pinfunction "1_1") (pintype "passive"))
    )
    (net (code "31") (name "SCL_3V") (class "Default")
      (node (ref "ALT_SENSOR") (pin "8") (pinfunction "SCL_8") (pintype "bidirectional"))
      (node (ref "Q2") (pin "2") (pinfunction "S_2") (pintype "bidirectional"))
      (node (ref "R1") (pin "1") (pinfunction "1_1") (pintype "passive"))
      (node (ref "U2") (pin "19") (pinfunction "COM1_19") (pintype "bidirectional"))
    )
    (net (code "32") (name "SCL_5V") (class "Default")
      (node (ref "KIT1") (pin "P$10") (pinfunction "P10_P$10") (pintype "bidirectional"))
      (node (ref "MOTOR") (pin "P$2") (pinfunction "SCL_P$2") (pintype "bidirectional"))
      (node (ref "Q2") (pin "3") (pinfunction "D_3") (pintype "bidirectional"))
      (node (ref "R5") (pin "1") (pinfunction "1_1") (pintype "passive"))
    )
    (net (code "33") (name "SDA(2)_5V") (class "Default")
      (node (ref "AT-328P") (pin "27") (pinfunction "PC4(ADC4/SDA)_27") (pintype "bidirectional"))
      (node (ref "KIT1") (pin "P$28") (pinfunction "P28_P$28") (pintype "bidirectional"))
      (node (ref "R8") (pin "1") (pinfunction "1_1") (pintype "passive"))
    )
    (net (code "34") (name "SDA_3V") (class "Default")
      (node (ref "ALT_SENSOR") (pin "7") (pinfunction "SDL_7") (pintype "bidirectional"))
      (node (ref "Q1") (pin "2") (pinfunction "S_2") (pintype "bidirectional"))
      (node (ref "R2") (pin "1") (pinfunction "1_1") (pintype "passive"))
      (node (ref "U2") (pin "20") (pinfunction "COM0_20") (pintype "bidirectional"))
    )
    (net (code "35") (name "SDA_5V") (class "Default")
      (node (ref "KIT1") (pin "P$9") (pinfunction "P9_P$9") (pintype "bidirectional"))
      (node (ref "MOTOR") (pin "P$3") (pinfunction "SDA_P$3") (pintype "bidirectional"))
      (node (ref "Q1") (pin "3") (pinfunction "D_3") (pintype "bidirectional"))
      (node (ref "R4") (pin "1") (pinfunction "1_1") (pintype "passive"))
    )
    (net (code "36") (name "VB") (class "Default")
      (node (ref "KIT1") (pin "VB") (pinfunction "VB_VB") (pintype "power_in"))
    )
    (net (code "37") (name "VIN") (class "Default")
      (node (ref "KIT1") (pin "VIN") (pinfunction "VIN_VIN") (pintype "power_in"))
    )
    (net (code "38") (name "VO") (class "Default")
      (node (ref "KIT1") (pin "VOUT") (pinfunction "VO_VOUT") (pintype "power_in"))
    )
    (net (code "39") (name "XIN_A") (class "Default")
      (node (ref "C7") (pin "1") (pinfunction "1_1") (pintype "passive"))
      (node (ref "U2") (pin "27") (pinfunction "XIN32_27") (pintype "input"))
      (node (ref "U3") (pin "4") (pinfunction "X2_4") (pintype "bidirectional"))
    )
    (net (code "40") (name "XOUT_A") (class "Default")
      (node (ref "C8") (pin "1") (pinfunction "1_1") (pintype "passive"))
      (node (ref "U2") (pin "26") (pinfunction "XOUT32_26") (pintype "output"))
      (node (ref "U3") (pin "1") (pinfunction "X1_1") (pintype "bidirectional"))
    )
    (net (code "41") (name "XTAL_A") (class "Default")
      (node (ref "AT-328P") (pin "7") (pinfunction "PB6(XTAL1/TOSC1)_7") (pintype "bidirectional"))
      (node (ref "XC") (pin "3") (pinfunction "3_3") (pintype "passive"))
    )
    (net (code "42") (name "XTAL_B") (class "Default")
      (node (ref "AT-328P") (pin "8") (pinfunction "PB7(XTAL2/TOSC2)_8") (pintype "bidirectional"))
      (node (ref "XC") (pin "1") (pinfunction "1_1") (pintype "passive"))
    )
    (net (code "43") (name "unconnected-(AT-328P-ADC6-Pad19)") (class "Default")
      (node (ref "AT-328P") (pin "19") (pinfunction "ADC6_19") (pintype "bidirectional"))
    )
    (net (code "44") (name "unconnected-(AT-328P-ADC7-Pad22)") (class "Default")
      (node (ref "AT-328P") (pin "22") (pinfunction "ADC7_22") (pintype "bidirectional"))
    )
    (net (code "45") (name "unconnected-(AT-328P-PB1(OC1A)-Pad13)") (class "Default")
      (node (ref "AT-328P") (pin "13") (pinfunction "PB1(OC1A)_13") (pintype "bidirectional"))
    )
    (net (code "46") (name "unconnected-(AT-328P-PB2(SS{slash}OC1B)-Pad14)") (class "Default")
      (node (ref "AT-328P") (pin "14") (pinfunction "PB2(SS/OC1B)_14") (pintype "bidirectional"))
    )
    (net (code "47") (name "unconnected-(AT-328P-PC0(ADC0)-Pad23)") (class "Default")
      (node (ref "AT-328P") (pin "23") (pinfunction "PC0(ADC0)_23") (pintype "bidirectional"))
    )
    (net (code "48") (name "unconnected-(AT-328P-PC1(ADC1)-Pad24)") (class "Default")
      (node (ref "AT-328P") (pin "24") (pinfunction "PC1(ADC1)_24") (pintype "bidirectional"))
    )
    (net (code "49") (name "unconnected-(AT-328P-PC2(ADC2)-Pad25)") (class "Default")
      (node (ref "AT-328P") (pin "25") (pinfunction "PC2(ADC2)_25") (pintype "bidirectional"))
    )
    (net (code "50") (name "unconnected-(AT-328P-PC3(ADC3)-Pad26)") (class "Default")
      (node (ref "AT-328P") (pin "26") (pinfunction "PC3(ADC3)_26") (pintype "bidirectional"))
    )
    (net (code "51") (name "unconnected-(AT-328P-PD0(RXD)-Pad30)") (class "Default")
      (node (ref "AT-328P") (pin "30") (pinfunction "PD0(RXD)_30") (pintype "bidirectional"))
    )
    (net (code "52") (name "unconnected-(AT-328P-PD1(TXD)-Pad31)") (class "Default")
      (node (ref "AT-328P") (pin "31") (pinfunction "PD1(TXD)_31") (pintype "bidirectional"))
    )
    (net (code "53") (name "unconnected-(AT-328P-PD2(INT0)-Pad32)") (class "Default")
      (node (ref "AT-328P") (pin "32") (pinfunction "PD2(INT0)_32") (pintype "bidirectional"))
    )
    (net (code "54") (name "unconnected-(AT-328P-PD3(INT1)-Pad1)") (class "Default")
      (node (ref "AT-328P") (pin "1") (pinfunction "PD3(INT1)_1") (pintype "bidirectional"))
    )
    (net (code "55") (name "unconnected-(AT-328P-PD4(XCK{slash}T0)-Pad2)") (class "Default")
      (node (ref "AT-328P") (pin "2") (pinfunction "PD4(XCK/T0)_2") (pintype "bidirectional"))
    )
    (net (code "56") (name "unconnected-(AT-328P-PD5(T1)-Pad9)") (class "Default")
      (node (ref "AT-328P") (pin "9") (pinfunction "PD5(T1)_9") (pintype "bidirectional"))
    )
    (net (code "57") (name "unconnected-(AT-328P-PD6(AIN0)-Pad10)") (class "Default")
      (node (ref "AT-328P") (pin "10") (pinfunction "PD6(AIN0)_10") (pintype "bidirectional"))
    )
    (net (code "58") (name "unconnected-(BX-P1-Pad4)") (class "Default")
      (node (ref "BX") (pin "4") (pinfunction "P1_4") (pintype "passive"))
    )
    (net (code "59") (name "unconnected-(BX-S1-Pad2)") (class "Default")
      (node (ref "BX") (pin "2") (pinfunction "S1_2") (pintype "passive"))
    )
    (net (code "60") (name "unconnected-(CANCEL-P1-Pad4)") (class "Default")
      (node (ref "CANCEL") (pin "4") (pinfunction "P1_4") (pintype "passive"))
    )
    (net (code "61") (name "unconnected-(CANCEL-S1-Pad2)") (class "Default")
      (node (ref "CANCEL") (pin "2") (pinfunction "S1_2") (pintype "passive"))
    )
    (net (code "62") (name "unconnected-(KIT1-P5-PadP$5)") (class "Default")
      (node (ref "KIT1") (pin "P$5") (pinfunction "P5_P$5") (pintype "bidirectional"))
    )
    (net (code "63") (name "unconnected-(KIT1-P6-PadP$6)") (class "Default")
      (node (ref "KIT1") (pin "P$6") (pinfunction "P6_P$6") (pintype "bidirectional"))
    )
    (net (code "64") (name "unconnected-(KIT1-P7-PadP$7)") (class "Default")
      (node (ref "KIT1") (pin "P$7") (pinfunction "P7_P$7") (pintype "bidirectional"))
    )
    (net (code "65") (name "unconnected-(KIT1-P8-PadP$8)") (class "Default")
      (node (ref "KIT1") (pin "P$8") (pinfunction "P8_P$8") (pintype "bidirectional"))
    )
    (net (code "66") (name "unconnected-(KIT1-P11-PadP$11)") (class "Default")
      (node (ref "KIT1") (pin "P$11") (pinfunction "P11_P$11") (pintype "bidirectional"))
    )
    (net (code "67") (name "unconnected-(KIT1-P12-PadP$12)") (class "Default")
      (node (ref "KIT1") (pin "P$12") (pinfunction "P12_P$12") (pintype "bidirectional"))
    )
    (net (code "68") (name "unconnected-(KIT1-P13-PadP$13)") (class "Default")
      (node (ref "KIT1") (pin "P$13") (pinfunction "P13_P$13") (pintype "bidirectional"))
    )
    (net (code "69") (name "unconnected-(KIT1-P14-PadP$14)") (class "Default")
      (node (ref "KIT1") (pin "P$14") (pinfunction "P14_P$14") (pintype "bidirectional"))
    )
    (net (code "70") (name "unconnected-(KIT1-P15-PadP$15)") (class "Default")
      (node (ref "KIT1") (pin "P$15") (pinfunction "P15_P$15") (pintype "bidirectional"))
    )
    (net (code "71") (name "unconnected-(KIT1-P16-PadP$16)") (class "Default")
      (node (ref "KIT1") (pin "P$16") (pinfunction "P16_P$16") (pintype "bidirectional"))
    )
    (net (code "72") (name "unconnected-(KIT1-P17-PadP$17)") (class "Default")
      (node (ref "KIT1") (pin "P$17") (pinfunction "P17_P$17") (pintype "bidirectional"))
    )
    (net (code "73") (name "unconnected-(KIT1-P18-PadP$18)") (class "Default")
      (node (ref "KIT1") (pin "P$18") (pinfunction "P18_P$18") (pintype "bidirectional"))
    )
    (net (code "74") (name "unconnected-(KIT1-P19-PadP$19)") (class "Default")
      (node (ref "KIT1") (pin "P$19") (pinfunction "P19_P$19") (pintype "bidirectional"))
    )
    (net (code "75") (name "unconnected-(KIT1-P20-PadP$20)") (class "Default")
      (node (ref "KIT1") (pin "P$20") (pinfunction "P20_P$20") (pintype "bidirectional"))
    )
    (net (code "76") (name "unconnected-(KIT1-PadIF+)") (class "Default")
      (node (ref "KIT1") (pin "IF+") (pinfunction "IF+_IF+") (pintype "bidirectional"))
    )
    (net (code "77") (name "unconnected-(KIT1-PadIF-)") (class "Default")
      (node (ref "KIT1") (pin "IF-") (pinfunction "IF-_IF-") (pintype "bidirectional"))
    )
    (net (code "78") (name "unconnected-(KIT1-PadRD+)") (class "Default")
      (node (ref "KIT1") (pin "RD+") (pinfunction "RD+_RD+") (pintype "bidirectional"))
    )
    (net (code "79") (name "unconnected-(KIT1-PadRD-)") (class "Default")
      (node (ref "KIT1") (pin "RD-") (pinfunction "RD-_RD-") (pintype "bidirectional"))
    )
    (net (code "80") (name "unconnected-(KIT1-PadTD+)") (class "Default")
      (node (ref "KIT1") (pin "TD+") (pinfunction "TD+_TD+") (pintype "bidirectional"))
    )
    (net (code "81") (name "unconnected-(KIT1-PadTD-)") (class "Default")
      (node (ref "KIT1") (pin "TD-") (pinfunction "TD-_TD-") (pintype "bidirectional"))
    )
    (net (code "82") (name "unconnected-(OK-P1-Pad4)") (class "Default")
      (node (ref "OK") (pin "4") (pinfunction "P1_4") (pintype "passive"))
    )
    (net (code "83") (name "unconnected-(OK-S1-Pad2)") (class "Default")
      (node (ref "OK") (pin "2") (pinfunction "S1_2") (pintype "passive"))
    )
    (net (code "84") (name "unconnected-(PANIC-P1-Pad4)") (class "Default")
      (node (ref "PANIC") (pin "4") (pinfunction "P1_4") (pintype "passive"))
    )
    (net (code "85") (name "unconnected-(PANIC-S1-Pad2)") (class "Default")
      (node (ref "PANIC") (pin "2") (pinfunction "S1_2") (pintype "passive"))
    )
    (net (code "86") (name "unconnected-(RST-P1-Pad4)") (class "Default")
      (node (ref "RST") (pin "4") (pinfunction "P1_4") (pintype "passive"))
    )
    (net (code "87") (name "unconnected-(RST-S1-Pad2)") (class "Default")
      (node (ref "RST") (pin "2") (pinfunction "S1_2") (pintype "passive"))
    )
    (net (code "88") (name "unconnected-(U1-BP-Pad4)") (class "Default")
      (node (ref "U1") (pin "4") (pinfunction "BP_4") (pintype "input"))
    )
  )
)
